# V1.net
KiCad netlist of a schematic drawn in EAGLE
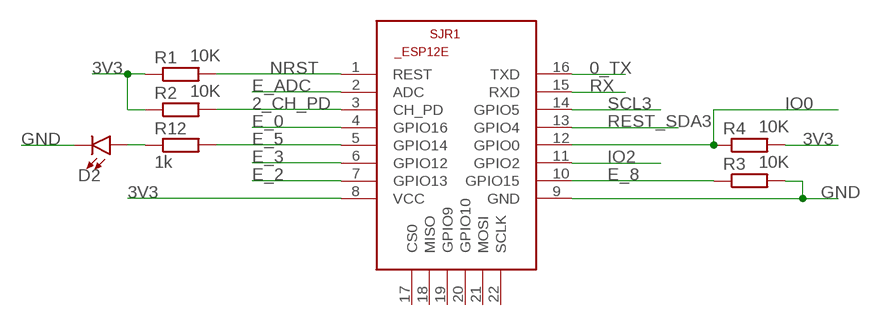
[diagram p0: schematic, sheet 1]
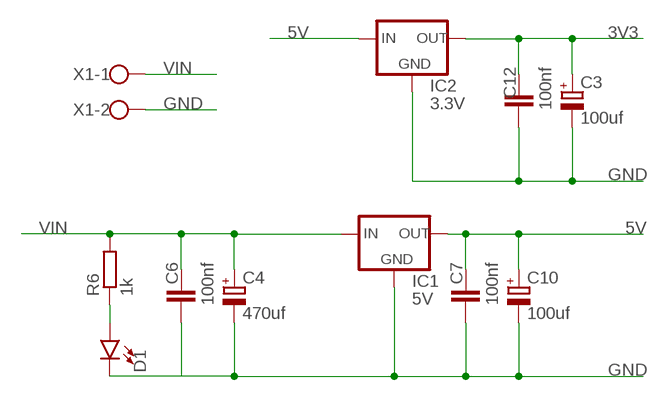
[diagram p1: schematic, sheet 2]
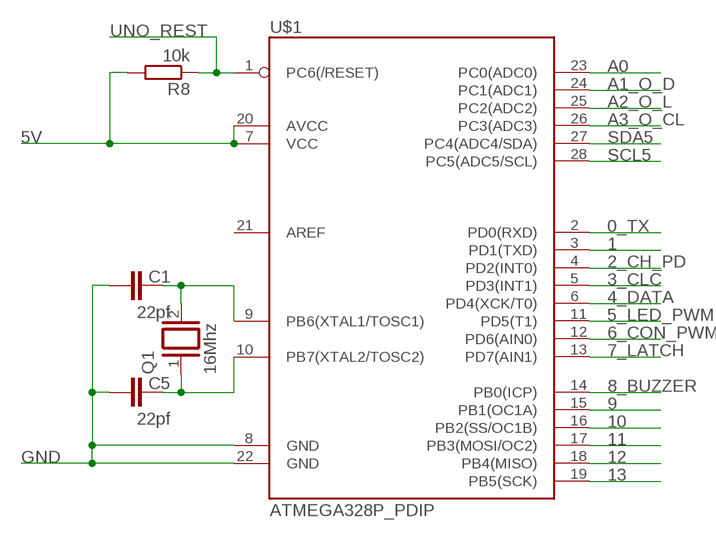
[diagram p2: schematic, sheet 3]
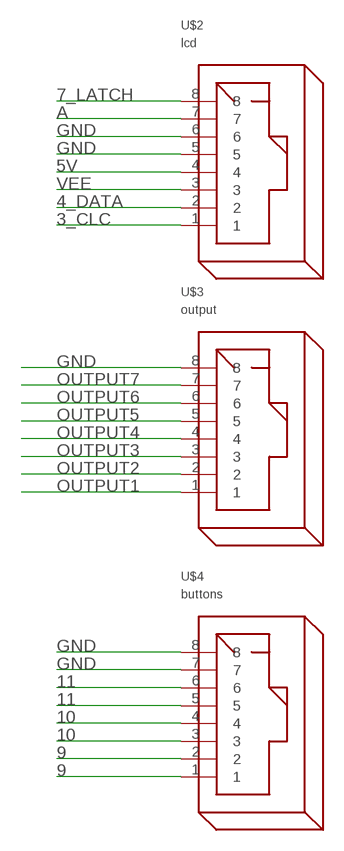
[diagram p3: schematic, sheet 4]
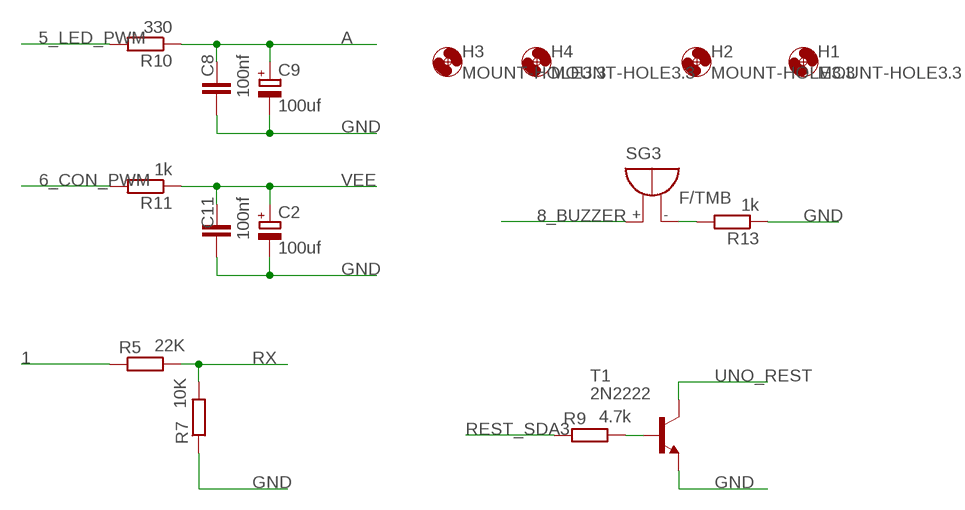
[diagram p4: schematic, sheet 5]
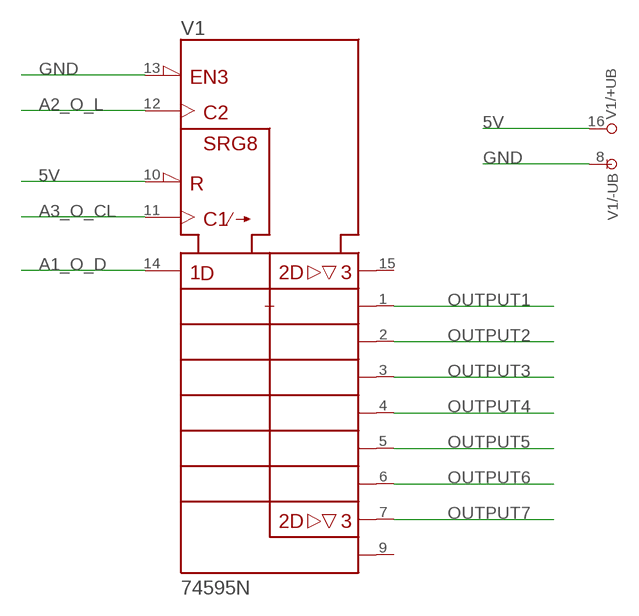
[diagram p5: schematic, sheet 6]

(export (version "E")
  (design (tool "Eeschema 10.0.6"))
  (components
    (comp (ref "C2")
      (value "100uf")
      (footprint "eagle-import:E3,5-8")
      (libsource (lib "eagle-import") (part "CPOL-EUE3.5-8"))
    )
    (comp (ref "C8")
      (value "100nf")
      (footprint "eagle-import:C050-030X075")
      (libsource (lib "eagle-import") (part "C-EU050-030X075"))
    )
    (comp (ref "C9")
      (value "100uf")
      (footprint "eagle-import:E3,5-8")
      (libsource (lib "eagle-import") (part "CPOL-EUE3.5-8"))
    )
    (comp (ref "C11")
      (value "100nf")
      (footprint "eagle-import:C050-030X075")
      (libsource (lib "eagle-import") (part "C-EU050-030X075"))
    )
    (comp (ref "H1")
      (value "MOUNT-HOLE3.3")
      (footprint "eagle-import:3,3")
      (libsource (lib "eagle-import") (part "MOUNT-HOLE3.3"))
    )
    (comp (ref "H2")
      (value "MOUNT-HOLE3.3")
      (footprint "eagle-import:3,3")
      (libsource (lib "eagle-import") (part "MOUNT-HOLE3.3"))
    )
    (comp (ref "H3")
      (value "MOUNT-HOLE3.3")
      (footprint "eagle-import:3,3")
      (libsource (lib "eagle-import") (part "MOUNT-HOLE3.3"))
    )
    (comp (ref "H4")
      (value "MOUNT-HOLE3.3")
      (footprint "eagle-import:3,3")
      (libsource (lib "eagle-import") (part "MOUNT-HOLE3.3"))
    )
    (comp (ref "R5")
      (value "22K")
      (footprint "eagle-import:0207_10")
      (libsource (lib "eagle-import") (part "rcl_334_R-EU_0207/10"))
    )
    (comp (ref "R7")
      (value "10K")
      (footprint "eagle-import:0207_10")
      (libsource (lib "eagle-import") (part "rcl_334_R-EU_0207/10"))
    )
    (comp (ref "R9")
      (value "4.7k")
      (footprint "eagle-import:0207_10")
      (libsource (lib "eagle-import") (part "rcl_334_R-EU_0207/10"))
    )
    (comp (ref "R10")
      (value "330")
      (footprint "eagle-import:0207_10")
      (libsource (lib "eagle-import") (part "R-EU_0207/10"))
    )
    (comp (ref "R11")
      (value "1k")
      (footprint "eagle-import:0207_10")
      (libsource (lib "eagle-import") (part "R-EU_0207/10"))
    )
    (comp (ref "R13")
      (value "1k")
      (footprint "eagle-import:0207_10")
      (libsource (lib "eagle-import") (part "R-EU_0207/10"))
    )
    (comp (ref "SG3")
      (value "F/TMB")
      (footprint "eagle-import:F_TMB")
      (libsource (lib "eagle-import") (part "F/TMB"))
    )
    (comp (ref "T1")
      (value "2N2222")
      (footprint "eagle-import:TO92-EBC-OVAL")
      (libsource (lib "eagle-import") (part "2N2222"))
    )
    (comp (ref "C1")
      (value "22pf")
      (footprint "eagle-import:C050-030X075")
      (libsource (lib "eagle-import") (part "C-EU050-030X075"))
    )
    (comp (ref "C5")
      (value "22pf")
      (footprint "eagle-import:C050-030X075")
      (libsource (lib "eagle-import") (part "C-EU050-030X075"))
    )
    (comp (ref "Q1")
      (value "16Mhz")
      (footprint "eagle-import:QS")
      (libsource (lib "eagle-import") (part "XTAL/S"))
    )
    (comp (ref "R8")
      (value "10k")
      (footprint "eagle-import:0207_10")
      (libsource (lib "eagle-import") (part "R-EU_0207/10"))
    )
    (comp (ref "U$1")
      (value "ATMEGA328P_PDIP")
      (footprint "eagle-import:DIL-28-3")
      (libsource (lib "eagle-import") (part "ATMEGA328P_PDIP"))
    )
    (comp (ref "D2")
      (value "LED5MM")
      (footprint "eagle-import:LED_5MM")
      (libsource (lib "eagle-import") (part "LED5MM"))
    )
    (comp (ref "R1")
      (value "10K")
      (footprint "eagle-import:0207_10")
      (libsource (lib "eagle-import") (part "rcl_334_R-EU_0207/10"))
    )
    (comp (ref "R2")
      (value "10K")
      (footprint "eagle-import:0207_10")
      (libsource (lib "eagle-import") (part "rcl_334_R-EU_0207/10"))
    )
    (comp (ref "R3")
      (value "10K")
      (footprint "eagle-import:0207_10")
      (libsource (lib "eagle-import") (part "rcl_334_R-EU_0207/10"))
    )
    (comp (ref "R4")
      (value "10K")
      (footprint "eagle-import:0207_10")
      (libsource (lib "eagle-import") (part "rcl_334_R-EU_0207/10"))
    )
    (comp (ref "R12")
      (value "1k")
      (footprint "eagle-import:0207_10")
      (libsource (lib "eagle-import") (part "R-EU_0207/10"))
    )
    (comp (ref "SJR1")
      (value "ESP8266-12EESP12E")
      (footprint "eagle-import:ESP8266-ESP12E")
      (libsource (lib "eagle-import") (part "ESP8266-12EESP12E"))
    )
    (comp (ref "V1")
      (value "74595N")
      (footprint "eagle-import:DIL16")
      (libsource (lib "eagle-import") (part "74595N"))
    )
    (comp (ref "C3")
      (value "100uf")
      (footprint "eagle-import:E3,5-8")
      (libsource (lib "eagle-import") (part "CPOL-EUE3.5-8"))
    )
    (comp (ref "C4")
      (value "470uf")
      (footprint "eagle-import:E3,5-8")
      (libsource (lib "eagle-import") (part "CPOL-EUE3.5-8"))
    )
    (comp (ref "C6")
      (value "100nf")
      (footprint "eagle-import:C050-030X075")
      (libsource (lib "eagle-import") (part "C-EU050-030X075"))
    )
    (comp (ref "C7")
      (value "100nf")
      (footprint "eagle-import:C050-030X075")
      (libsource (lib "eagle-import") (part "C-EU050-030X075"))
    )
    (comp (ref "C10")
      (value "100uf")
      (footprint "eagle-import:E3,5-8")
      (libsource (lib "eagle-import") (part "CPOL-EUE3.5-8"))
    )
    (comp (ref "C12")
      (value "100nf")
      (footprint "eagle-import:C050-030X075")
      (libsource (lib "eagle-import") (part "C-EU050-030X075"))
    )
    (comp (ref "D1")
      (value "LED5MM")
      (footprint "eagle-import:LED_5MM")
      (libsource (lib "eagle-import") (part "LED5MM"))
    )
    (comp (ref "IC1")
      (value "5V")
      (footprint "eagle-import:78XXL")
      (libsource (lib "eagle-import") (part "V_REG_78XXSIDE"))
    )
    (comp (ref "IC2")
      (value "3.3V")
      (footprint "eagle-import:78XXL")
      (libsource (lib "eagle-import") (part "V_REG_78XXSIDE"))
    )
    (comp (ref "R6")
      (value "1k")
      (footprint "eagle-import:0207_10")
      (libsource (lib "eagle-import") (part "R-EU_0207/10"))
    )
    (comp (ref "X1")
      (value "W237-102")
      (footprint "eagle-import:W237-102")
      (fields (field (name "MPN") "237-102"))
      (libsource (lib "eagle-import") (part "W237-102"))
    )
    (comp (ref "U$2")
      (value "lcd")
      (footprint "eagle-import:RJ45")
      (libsource (lib "eagle-import") (part "RJ45"))
    )
    (comp (ref "U$3")
      (value "output")
      (footprint "eagle-import:RJ45")
      (libsource (lib "eagle-import") (part "RJ45"))
    )
    (comp (ref "U$4")
      (value "buttons")
      (footprint "eagle-import:RJ45")
      (libsource (lib "eagle-import") (part "RJ45"))
    )
  )
  (nets
    (net (code "1") (name "0_TX") (class "Default")
      (node (ref "SJR1") (pin "16") (pinfunction "TXD_16") (pintype "bidirectional"))
      (node (ref "U$1") (pin "2") (pinfunction "PD0(RXD)_2") (pintype "bidirectional"))
    )
    (net (code "2") (name "1") (class "Default")
      (node (ref "R5") (pin "1") (pinfunction "1_1") (pintype "passive"))
      (node (ref "U$1") (pin "3") (pinfunction "PD1(TXD)_3") (pintype "bidirectional"))
    )
    (net (code "3") (name "2_CH_PD") (class "Default")
      (node (ref "R2") (pin "2") (pinfunction "2_2") (pintype "passive"))
      (node (ref "SJR1") (pin "3") (pinfunction "CH_PD_3") (pintype "bidirectional"))
      (node (ref "U$1") (pin "4") (pinfunction "PD2(INT0)_4") (pintype "bidirectional"))
    )
    (net (code "4") (name "3V3") (class "Default")
      (node (ref "C12") (pin "2") (pinfunction "2_2") (pintype "passive"))
      (node (ref "C3") (pin "+") (pinfunction "+_+") (pintype "passive"))
      (node (ref "IC2") (pin "OUT") (pinfunction "OUT_OUT") (pintype "output"))
      (node (ref "R1") (pin "1") (pinfunction "1_1") (pintype "passive"))
      (node (ref "R2") (pin "1") (pinfunction "1_1") (pintype "passive"))
      (node (ref "R4") (pin "2") (pinfunction "2_2") (pintype "passive"))
      (node (ref "SJR1") (pin "8") (pinfunction "VCC_8") (pintype "bidirectional"))
    )
    (net (code "5") (name "3_CLC") (class "Default")
      (node (ref "U$1") (pin "5") (pinfunction "PD3(INT1)_5") (pintype "bidirectional"))
      (node (ref "U$2") (pin "1") (pinfunction "1_1") (pintype "bidirectional"))
    )
    (net (code "6") (name "4_DATA") (class "Default")
      (node (ref "U$1") (pin "6") (pinfunction "PD4(XCK/T0)_6") (pintype "bidirectional"))
      (node (ref "U$2") (pin "2") (pinfunction "2_2") (pintype "bidirectional"))
    )
    (net (code "7") (name "5V") (class "Default")
      (node (ref "C10") (pin "+") (pinfunction "+_+") (pintype "passive"))
      (node (ref "C7") (pin "2") (pinfunction "2_2") (pintype "passive"))
      (node (ref "IC1") (pin "OUT") (pinfunction "OUT_OUT") (pintype "output"))
      (node (ref "IC2") (pin "IN") (pinfunction "IN_IN") (pintype "input"))
      (node (ref "R8") (pin "2") (pinfunction "2_2") (pintype "passive"))
      (node (ref "U$1") (pin "20") (pinfunction "AVCC_20") (pintype "bidirectional"))
      (node (ref "U$1") (pin "7") (pinfunction "VCC_7") (pintype "bidirectional"))
      (node (ref "U$2") (pin "4") (pinfunction "4_4") (pintype "bidirectional"))
      (node (ref "V1") (pin "10") (pinfunction "~{SRCLR}_10") (pintype "input"))
      (node (ref "V1") (pin "16") (pinfunction "+UB_16") (pintype "power_in"))
    )
    (net (code "8") (name "5_LED_PWM") (class "Default")
      (node (ref "R10") (pin "2") (pinfunction "2_2") (pintype "passive"))
      (node (ref "U$1") (pin "11") (pinfunction "PD5(T1)_11") (pintype "bidirectional"))
    )
    (net (code "9") (name "6_CON_PWM") (class "Default")
      (node (ref "R11") (pin "2") (pinfunction "2_2") (pintype "passive"))
      (node (ref "U$1") (pin "12") (pinfunction "PD6(AIN0)_12") (pintype "bidirectional"))
    )
    (net (code "10") (name "7_LATCH") (class "Default")
      (node (ref "U$1") (pin "13") (pinfunction "PD7(AIN1)_13") (pintype "bidirectional"))
      (node (ref "U$2") (pin "8") (pinfunction "8_8") (pintype "bidirectional"))
    )
    (net (code "11") (name "8_BUZZER") (class "Default")
      (node (ref "SG3") (pin "+") (pinfunction "+_+") (pintype "passive"))
      (node (ref "U$1") (pin "14") (pinfunction "PB0(ICP)_14") (pintype "bidirectional"))
    )
    (net (code "12") (name "9") (class "Default")
      (node (ref "U$1") (pin "15") (pinfunction "PB1(OC1A)_15") (pintype "bidirectional"))
      (node (ref "U$4") (pin "1") (pinfunction "1_1") (pintype "bidirectional"))
      (node (ref "U$4") (pin "2") (pinfunction "2_2") (pintype "bidirectional"))
    )
    (net (code "13") (name "10") (class "Default")
      (node (ref "U$1") (pin "16") (pinfunction "PB2(SS/OC1B)_16") (pintype "bidirectional"))
      (node (ref "U$4") (pin "3") (pinfunction "3_3") (pintype "bidirectional"))
      (node (ref "U$4") (pin "4") (pinfunction "4_4") (pintype "bidirectional"))
    )
    (net (code "14") (name "11") (class "Default")
      (node (ref "U$1") (pin "17") (pinfunction "PB3(MOSI/OC2)_17") (pintype "bidirectional"))
      (node (ref "U$4") (pin "5") (pinfunction "5_5") (pintype "bidirectional"))
      (node (ref "U$4") (pin "6") (pinfunction "6_6") (pintype "bidirectional"))
    )
    (net (code "15") (name "12") (class "Default")
      (node (ref "U$1") (pin "18") (pinfunction "PB4(MISO)_18") (pintype "bidirectional"))
    )
    (net (code "16") (name "13") (class "Default")
      (node (ref "U$1") (pin "19") (pinfunction "PB5(SCK)_19") (pintype "bidirectional"))
    )
    (net (code "17") (name "A") (class "Default")
      (node (ref "C8") (pin "2") (pinfunction "2_2") (pintype "passive"))
      (node (ref "C9") (pin "+") (pinfunction "+_+") (pintype "passive"))
      (node (ref "R10") (pin "1") (pinfunction "1_1") (pintype "passive"))
      (node (ref "U$2") (pin "7") (pinfunction "7_7") (pintype "bidirectional"))
    )
    (net (code "18") (name "A0") (class "Default")
      (node (ref "U$1") (pin "23") (pinfunction "PC0(ADC0)_23") (pintype "bidirectional"))
    )
    (net (code "19") (name "A1_O_D") (class "Default")
      (node (ref "U$1") (pin "24") (pinfunction "PC1(ADC1)_24") (pintype "bidirectional"))
      (node (ref "V1") (pin "14") (pinfunction "SER_14") (pintype "input"))
    )
    (net (code "20") (name "A2_O_L") (class "Default")
      (node (ref "U$1") (pin "25") (pinfunction "PC2(ADC2)_25") (pintype "bidirectional"))
      (node (ref "V1") (pin "12") (pinfunction "RCK_12") (pintype "input"))
    )
    (net (code "21") (name "A3_O_CL") (class "Default")
      (node (ref "U$1") (pin "26") (pinfunction "PC3(ADC3)_26") (pintype "bidirectional"))
      (node (ref "V1") (pin "11") (pinfunction "SRCK_11") (pintype "input"))
    )
    (net (code "22") (name "E_0") (class "Default")
      (node (ref "SJR1") (pin "4") (pinfunction "GPIO16_4") (pintype "bidirectional"))
    )
    (net (code "23") (name "E_2") (class "Default")
      (node (ref "SJR1") (pin "7") (pinfunction "GPIO13_7") (pintype "bidirectional"))
    )
    (net (code "24") (name "E_3") (class "Default")
      (node (ref "SJR1") (pin "6") (pinfunction "GPIO12_6") (pintype "bidirectional"))
    )
    (net (code "25") (name "E_5") (class "Default")
      (node (ref "R12") (pin "2") (pinfunction "2_2") (pintype "passive"))
      (node (ref "SJR1") (pin "5") (pinfunction "GPIO14_5") (pintype "bidirectional"))
    )
    (net (code "26") (name "E_8") (class "Default")
      (node (ref "R3") (pin "1") (pinfunction "1_1") (pintype "passive"))
      (node (ref "SJR1") (pin "10") (pinfunction "GPIO15_10") (pintype "bidirectional"))
    )
    (net (code "27") (name "E_ADC") (class "Default")
      (node (ref "SJR1") (pin "2") (pinfunction "ADC_2") (pintype "bidirectional"))
    )
    (net (code "28") (name "GND") (class "Default")
      (node (ref "C1") (pin "1") (pinfunction "1_1") (pintype "passive"))
      (node (ref "C10") (pin "-") (pinfunction "-_-") (pintype "passive"))
      (node (ref "C11") (pin "1") (pinfunction "1_1") (pintype "passive"))
      (node (ref "C12") (pin "1") (pinfunction "1_1") (pintype "passive"))
      (node (ref "C2") (pin "-") (pinfunction "-_-") (pintype "passive"))
      (node (ref "C3") (pin "-") (pinfunction "-_-") (pintype "passive"))
      (node (ref "C4") (pin "-") (pinfunction "-_-") (pintype "passive"))
      (node (ref "C5") (pin "1") (pinfunction "1_1") (pintype "passive"))
      (node (ref "C6") (pin "1") (pinfunction "1_1") (pintype "passive"))
      (node (ref "C7") (pin "1") (pinfunction "1_1") (pintype "passive"))
      (node (ref "C8") (pin "1") (pinfunction "1_1") (pintype "passive"))
      (node (ref "C9") (pin "-") (pinfunction "-_-") (pintype "passive"))
      (node (ref "D1") (pin "K") (pinfunction "C_K") (pintype "passive"))
      (node (ref "D2") (pin "K") (pinfunction "C_K") (pintype "passive"))
      (node (ref "IC1") (pin "GND") (pinfunction "GND_GND") (pintype "input"))
      (node (ref "IC2") (pin "GND") (pinfunction "GND_GND") (pintype "input"))
      (node (ref "R13") (pin "1") (pinfunction "1_1") (pintype "passive"))
      (node (ref "R3") (pin "2") (pinfunction "2_2") (pintype "passive"))
      (node (ref "R7") (pin "1") (pinfunction "1_1") (pintype "passive"))
      (node (ref "SJR1") (pin "9") (pinfunction "GND_9") (pintype "bidirectional"))
      (node (ref "T1") (pin "E") (pinfunction "E_E") (pintype "passive"))
      (node (ref "U$1") (pin "22") (pinfunction "GND_22") (pintype "bidirectional"))
      (node (ref "U$1") (pin "8") (pinfunction "GND_8") (pintype "bidirectional"))
      (node (ref "U$2") (pin "5") (pinfunction "5_5") (pintype "bidirectional"))
      (node (ref "U$2") (pin "6") (pinfunction "6_6") (pintype "bidirectional"))
      (node (ref "U$3") (pin "8") (pinfunction "8_8") (pintype "bidirectional"))
      (node (ref "U$4") (pin "7") (pinfunction "7_7") (pintype "bidirectional"))
      (node (ref "U$4") (pin "8") (pinfunction "8_8") (pintype "bidirectional"))
      (node (ref "V1") (pin "13") (pinfunction "~{G}_13") (pintype "input"))
      (node (ref "V1") (pin "8") (pinfunction "-UB_8") (pintype "power_in"))
      (node (ref "X1") (pin "2") (pinfunction "KL_2") (pintype "passive"))
    )
    (net (code "29") (name "IO0") (class "Default")
      (node (ref "R4") (pin "1") (pinfunction "1_1") (pintype "passive"))
      (node (ref "SJR1") (pin "12") (pinfunction "GPIO0_12") (pintype "bidirectional"))
    )
    (net (code "30") (name "IO2") (class "Default")
      (node (ref "SJR1") (pin "11") (pinfunction "GPIO2_11") (pintype "bidirectional"))
    )
    (net (code "31") (name "NRST") (class "Default")
      (node (ref "R1") (pin "2") (pinfunction "2_2") (pintype "passive"))
      (node (ref "SJR1") (pin "1") (pinfunction "REST_1") (pintype "bidirectional"))
    )
    (net (code "32") (name "Net-(D1-PadA)") (class "Default")
      (node (ref "D1") (pin "A") (pinfunction "A_A") (pintype "passive"))
      (node (ref "R6") (pin "1") (pinfunction "1_1") (pintype "passive"))
    )
    (net (code "33") (name "Net-(D2-PadA)") (class "Default")
      (node (ref "D2") (pin "A") (pinfunction "A_A") (pintype "passive"))
      (node (ref "R12") (pin "1") (pinfunction "1_1") (pintype "passive"))
    )
    (net (code "34") (name "Net-(R9-Pad2)") (class "Default")
      (node (ref "R9") (pin "2") (pinfunction "2_2") (pintype "passive"))
      (node (ref "T1") (pin "B") (pinfunction "B_B") (pintype "passive"))
    )
    (net (code "35") (name "Net-(R13-Pad2)") (class "Default")
      (node (ref "R13") (pin "2") (pinfunction "2_2") (pintype "passive"))
      (node (ref "SG3") (pin "-") (pinfunction "-_-") (pintype "passive"))
    )
    (net (code "36") (name "Net-(U$1-PB6(XTAL1{slash}TOSC1))") (class "Default")
      (node (ref "C1") (pin "2") (pinfunction "2_2") (pintype "passive"))
      (node (ref "Q1") (pin "2") (pinfunction "2_2") (pintype "passive"))
      (node (ref "U$1") (pin "9") (pinfunction "PB6(XTAL1/TOSC1)_9") (pintype "bidirectional"))
    )
    (net (code "37") (name "Net-(U$1-PB7(XTAL2{slash}TOSC2))") (class "Default")
      (node (ref "C5") (pin "2") (pinfunction "2_2") (pintype "passive"))
      (node (ref "Q1") (pin "1") (pinfunction "1_1") (pintype "passive"))
      (node (ref "U$1") (pin "10") (pinfunction "PB7(XTAL2/TOSC2)_10") (pintype "bidirectional"))
    )
    (net (code "38") (name "OUTPUT1") (class "Default")
      (node (ref "U$3") (pin "1") (pinfunction "1_1") (pintype "bidirectional"))
      (node (ref "V1") (pin "1") (pinfunction "QB_1") (pintype "tri_state"))
    )
    (net (code "39") (name "OUTPUT2") (class "Default")
      (node (ref "U$3") (pin "2") (pinfunction "2_2") (pintype "bidirectional"))
      (node (ref "V1") (pin "2") (pinfunction "QC_2") (pintype "tri_state"))
    )
    (net (code "40") (name "OUTPUT3") (class "Default")
      (node (ref "U$3") (pin "3") (pinfunction "3_3") (pintype "bidirectional"))
      (node (ref "V1") (pin "3") (pinfunction "QD_3") (pintype "tri_state"))
    )
    (net (code "41") (name "OUTPUT4") (class "Default")
      (node (ref "U$3") (pin "4") (pinfunction "4_4") (pintype "bidirectional"))
      (node (ref "V1") (pin "4") (pinfunction "QE_4") (pintype "tri_state"))
    )
    (net (code "42") (name "OUTPUT5") (class "Default")
      (node (ref "U$3") (pin "5") (pinfunction "5_5") (pintype "bidirectional"))
      (node (ref "V1") (pin "5") (pinfunction "QF_5") (pintype "tri_state"))
    )
    (net (code "43") (name "OUTPUT6") (class "Default")
      (node (ref "U$3") (pin "6") (pinfunction "6_6") (pintype "bidirectional"))
      (node (ref "V1") (pin "6") (pinfunction "QG_6") (pintype "tri_state"))
    )
    (net (code "44") (name "OUTPUT7") (class "Default")
      (node (ref "U$3") (pin "7") (pinfunction "7_7") (pintype "bidirectional"))
      (node (ref "V1") (pin "7") (pinfunction "QH_7") (pintype "tri_state"))
    )
    (net (code "45") (name "REST_SDA3") (class "Default")
      (node (ref "R9") (pin "1") (pinfunction "1_1") (pintype "passive"))
      (node (ref "SJR1") (pin "13") (pinfunction "GPIO4_13") (pintype "bidirectional"))
    )
    (net (code "46") (name "RX") (class "Default")
      (node (ref "R5") (pin "2") (pinfunction "2_2") (pintype "passive"))
      (node (ref "R7") (pin "2") (pinfunction "2_2") (pintype "passive"))
      (node (ref "SJR1") (pin "15") (pinfunction "RXD_15") (pintype "bidirectional"))
    )
    (net (code "47") (name "SCL3") (class "Default")
      (node (ref "SJR1") (pin "14") (pinfunction "GPIO5_14") (pintype "bidirectional"))
    )
    (net (code "48") (name "SCL5") (class "Default")
      (node (ref "U$1") (pin "28") (pinfunction "PC5(ADC5/SCL)_28") (pintype "bidirectional"))
    )
    (net (code "49") (name "SDA5") (class "Default")
      (node (ref "U$1") (pin "27") (pinfunction "PC4(ADC4/SDA)_27") (pintype "bidirectional"))
    )
    (net (code "50") (name "UNO_REST") (class "Default")
      (node (ref "R8") (pin "1") (pinfunction "1_1") (pintype "passive"))
      (node (ref "T1") (pin "C") (pinfunction "C_C") (pintype "passive"))
      (node (ref "U$1") (pin "1") (pinfunction "PC6(/RESET)_1") (pintype "bidirectional"))
    )
    (net (code "51") (name "VEE") (class "Default")
      (node (ref "C11") (pin "2") (pinfunction "2_2") (pintype "passive"))
      (node (ref "C2") (pin "+") (pinfunction "+_+") (pintype "passive"))
      (node (ref "R11") (pin "1") (pinfunction "1_1") (pintype "passive"))
      (node (ref "U$2") (pin "3") (pinfunction "3_3") (pintype "bidirectional"))
    )
    (net (code "52") (name "VIN") (class "Default")
      (node (ref "C4") (pin "+") (pinfunction "+_+") (pintype "passive"))
      (node (ref "C6") (pin "2") (pinfunction "2_2") (pintype "passive"))
      (node (ref "IC1") (pin "IN") (pinfunction "IN_IN") (pintype "input"))
      (node (ref "R6") (pin "2") (pinfunction "2_2") (pintype "passive"))
      (node (ref "X1") (pin "1") (pinfunction "KL_1") (pintype "passive"))
    )
    (net (code "53") (name "unconnected-(SJR1-CS0-Pad17)") (class "Default")
      (node (ref "SJR1") (pin "17") (pinfunction "CS0_17") (pintype "bidirectional"))
    )
    (net (code "54") (name "unconnected-(SJR1-GPIO9-Pad19)") (class "Default")
      (node (ref "SJR1") (pin "19") (pinfunction "GPIO9_19") (pintype "bidirectional"))
    )
    (net (code "55") (name "unconnected-(SJR1-GPIO10-Pad20)") (class "Default")
      (node (ref "SJR1") (pin "20") (pinfunction "GPIO10_20") (pintype "bidirectional"))
    )
    (net (code "56") (name "unconnected-(SJR1-MISO-Pad18)") (class "Default")
      (node (ref "SJR1") (pin "18") (pinfunction "MISO_18") (pintype "bidirectional"))
    )
    (net (code "57") (name "unconnected-(SJR1-MOSI-Pad21)") (class "Default")
      (node (ref "SJR1") (pin "21") (pinfunction "MOSI_21") (pintype "bidirectional"))
    )
    (net (code "58") (name "unconnected-(SJR1-SCLK-Pad22)") (class "Default")
      (node (ref "SJR1") (pin "22") (pinfunction "SCLK_22") (pintype "bidirectional"))
    )
    (net (code "59") (name "unconnected-(U$1-AREF-Pad21)") (class "Default")
      (node (ref "U$1") (pin "21") (pinfunction "AREF_21") (pintype "bidirectional"))
    )
    (net (code "60") (name "unconnected-(V1C-QA-Pad15)") (class "Default")
      (node (ref "V1") (pin "15") (pinfunction "QA_15") (pintype "tri_state"))
    )
    (net (code "61") (name "unconnected-(V1C-QH*-Pad9)") (class "Default")
      (node (ref "V1") (pin "9") (pinfunction "QH*_9") (pintype "output"))
    )
  )
)
